# MUX_gate.net
KiCad netlist of a schematic drawn in EAGLE
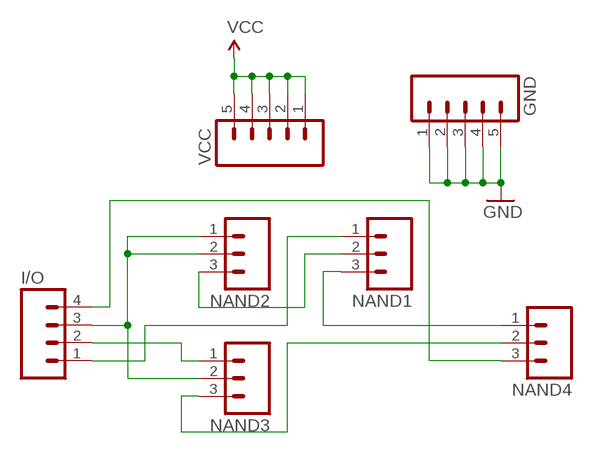
[diagram p0: schematic, sheet 1]

(export (version "E")
  (design (tool "Eeschema 10.0.6"))
  (components
    (comp (ref "GND")
      (value "M05LOCK")
      (footprint "eagle-import:1X05_LOCK")
      (libsource (lib "eagle-import") (part "M05LOCK"))
    )
    (comp (ref "I/O")
      (value "M04LOCK")
      (footprint "eagle-import:1X04_LOCK")
      (libsource (lib "eagle-import") (part "M04LOCK"))
    )
    (comp (ref "NAND1")
      (value "M03LOCK")
      (footprint "eagle-import:1X03_LOCK")
      (libsource (lib "eagle-import") (part "M03LOCK"))
    )
    (comp (ref "NAND2")
      (value "M03LOCK")
      (footprint "eagle-import:1X03_LOCK")
      (libsource (lib "eagle-import") (part "M03LOCK"))
    )
    (comp (ref "NAND3")
      (value "M03LOCK")
      (footprint "eagle-import:1X03_LOCK")
      (libsource (lib "eagle-import") (part "M03LOCK"))
    )
    (comp (ref "NAND4")
      (value "M03LOCK")
      (footprint "eagle-import:1X03_LOCK")
      (libsource (lib "eagle-import") (part "M03LOCK"))
    )
    (comp (ref "VCC")
      (value "M05LOCK")
      (footprint "eagle-import:1X05_LOCK")
      (libsource (lib "eagle-import") (part "M05LOCK"))
    )
  )
  (nets
    (net (code "1") (name "GND") (class "Default")
      (node (ref "GND") (pin "1") (pinfunction "1_1") (pintype "passive"))
      (node (ref "GND") (pin "2") (pinfunction "2_2") (pintype "passive"))
      (node (ref "GND") (pin "3") (pinfunction "3_3") (pintype "passive"))
      (node (ref "GND") (pin "4") (pinfunction "4_4") (pintype "passive"))
      (node (ref "GND") (pin "5") (pinfunction "5_5") (pintype "passive"))
    )
    (net (code "2") (name "Net-(I/O-Pad1)") (class "Default")
      (node (ref "I/O") (pin "1") (pinfunction "1_1") (pintype "passive"))
      (node (ref "NAND1") (pin "1") (pinfunction "1_1") (pintype "passive"))
    )
    (net (code "3") (name "Net-(I/O-Pad2)") (class "Default")
      (node (ref "I/O") (pin "2") (pinfunction "2_2") (pintype "passive"))
      (node (ref "NAND3") (pin "1") (pinfunction "1_1") (pintype "passive"))
    )
    (net (code "4") (name "Net-(I/O-Pad3)") (class "Default")
      (node (ref "I/O") (pin "3") (pinfunction "3_3") (pintype "passive"))
      (node (ref "NAND2") (pin "1") (pinfunction "1_1") (pintype "passive"))
      (node (ref "NAND2") (pin "2") (pinfunction "2_2") (pintype "passive"))
      (node (ref "NAND3") (pin "2") (pinfunction "2_2") (pintype "passive"))
    )
    (net (code "5") (name "Net-(I/O-Pad4)") (class "Default")
      (node (ref "I/O") (pin "4") (pinfunction "4_4") (pintype "passive"))
      (node (ref "NAND4") (pin "3") (pinfunction "3_3") (pintype "passive"))
    )
    (net (code "6") (name "Net-(NAND1-Pad2)") (class "Default")
      (node (ref "NAND1") (pin "2") (pinfunction "2_2") (pintype "passive"))
      (node (ref "NAND2") (pin "3") (pinfunction "3_3") (pintype "passive"))
    )
    (net (code "7") (name "Net-(NAND1-Pad3)") (class "Default")
      (node (ref "NAND1") (pin "3") (pinfunction "3_3") (pintype "passive"))
      (node (ref "NAND4") (pin "1") (pinfunction "1_1") (pintype "passive"))
    )
    (net (code "8") (name "Net-(NAND3-Pad3)") (class "Default")
      (node (ref "NAND3") (pin "3") (pinfunction "3_3") (pintype "passive"))
      (node (ref "NAND4") (pin "2") (pinfunction "2_2") (pintype "passive"))
    )
    (net (code "9") (name "VCC") (class "Default")
      (node (ref "VCC") (pin "1") (pinfunction "1_1") (pintype "passive"))
      (node (ref "VCC") (pin "2") (pinfunction "2_2") (pintype "passive"))
      (node (ref "VCC") (pin "3") (pinfunction "3_3") (pintype "passive"))
      (node (ref "VCC") (pin "4") (pinfunction "4_4") (pintype "passive"))
      (node (ref "VCC") (pin "5") (pinfunction "5_5") (pintype "passive"))
    )
  )
)
